# Sheet1.net
KiCad netlist of a schematic drawn in Altium Designer
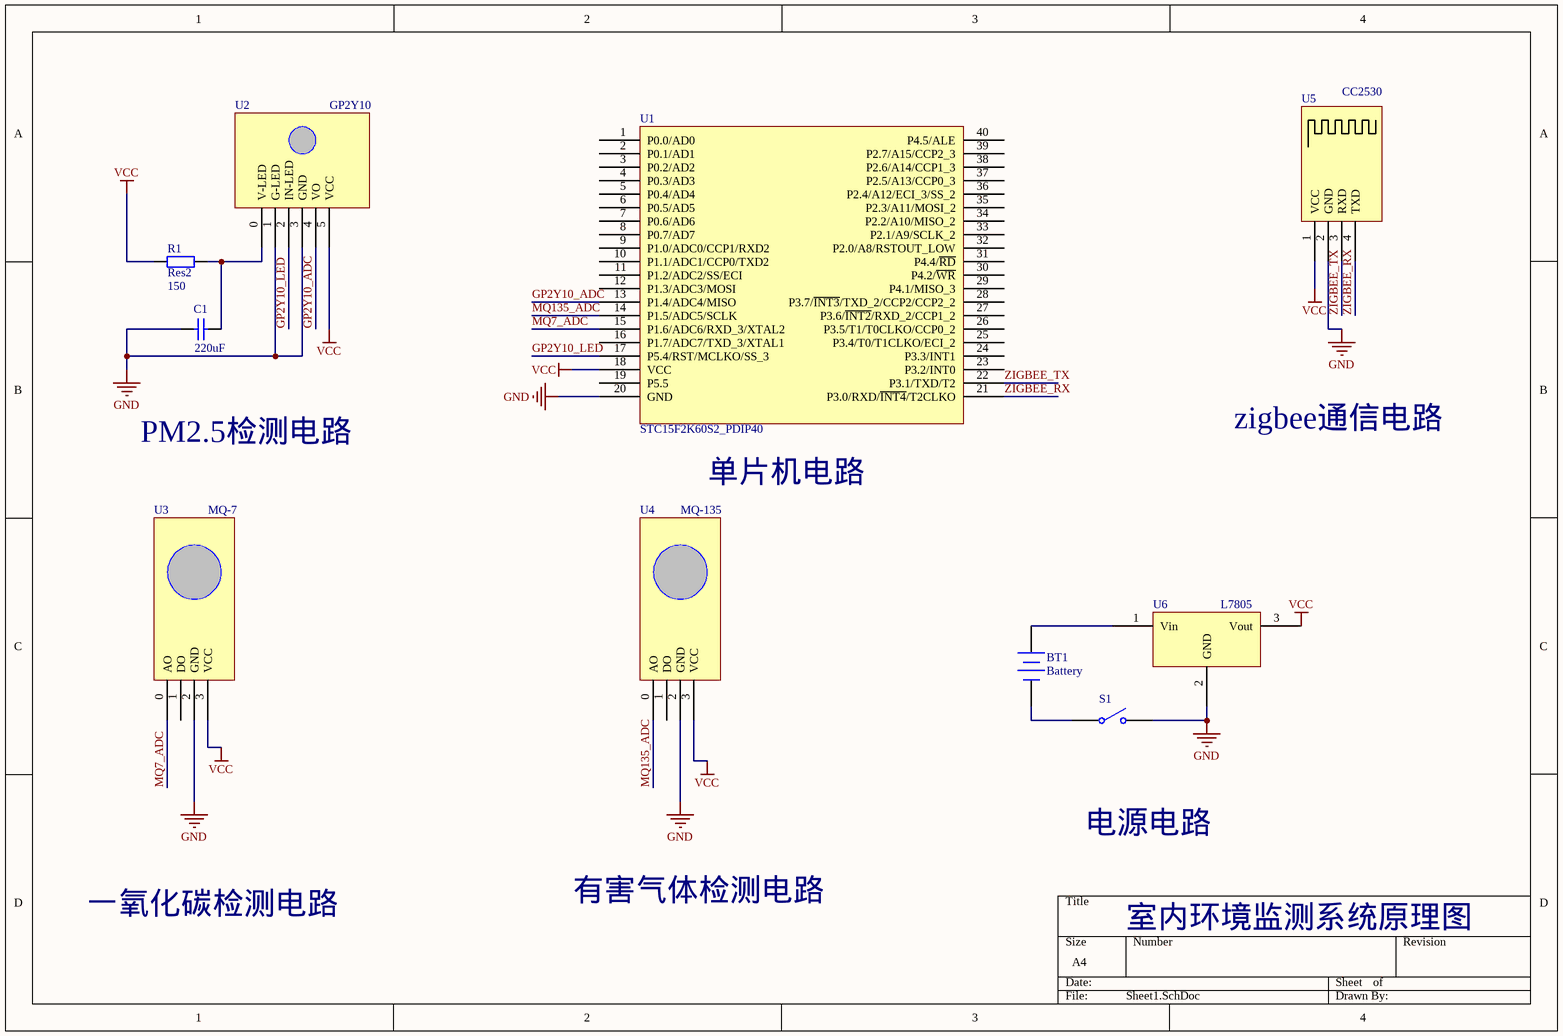
[diagram p0: Sheet1.SchDoc]

(export (version "E")
  (design (tool "Eeschema 10.0.6"))
  (components
    (comp (ref "BT1")
      (value "Battery")
      (footprint "BAT-2")
      (description "Multicell Battery")
      (fields (field (name "PUBLISHER") "Altium Limited"))
      (libsource (lib "Miscellaneous Devices") (part "Battery"))
    )
    (comp (ref "C1")
      (value "220uF")
      (footprint "RAD-0.3")
      (description "Capacitor")
      (fields (field (name "Comment") "Cap") (field (name "PUBLISHER") "Altium Limited"))
      (libsource (lib "Miscellaneous Devices") (part "Cap"))
    )
    (comp (ref "GP2Y10") (value "U2") (libsource (lib "Schlib1") (part "GP2Y10")))
    (comp (ref "R1")
      (value "Res2")
      (footprint "AXIAL-0.4")
      (description "Resistor")
      (fields (field (name "ALTIUM_VALUE") "150") (field (name "PUBLISHER") "Altium Limited"))
      (libsource (lib "Miscellaneous Devices") (part "Res2"))
    )
    (comp (ref "S1")
      (value "SW-SPST")
      (footprint "SPST-2")
      (description "Single-Pole, Single-Throw Switch")
      (fields (field (name "PUBLISHER") "Altium Limited"))
      (libsource (lib "Miscellaneous Devices") (part "SW-SPST"))
    )
    (comp (ref "U1")
      (value "STC15F2K60S2_PDIP40")
      (footprint "DIP40")
      (libsource (lib "stcmcu_altium_lib") (part "STC15F2K60S2_PDIP40"))
    )
    (comp (ref "U3") (value "MQ-7") (libsource (lib "Schlib1") (part "MQ-")))
    (comp (ref "U4") (value "MQ-135") (libsource (lib "Schlib1") (part "MQ-")))
    (comp (ref "U5") (value "CC2530") (libsource (lib "Schlib1") (part "CC2530")))
    (comp (ref "U6") (value "L7805") (libsource (lib "Schlib1") (part "L7805")))
  )
  (nets
    (net (code "1") (name "/GP2Y10_ADC") (class "Default")
      (node (ref "GP2Y10") (pin "4") (pinfunction "VO_4") (pintype "passive"))
      (node (ref "U1") (pin "13") (pinfunction "P1.4/ADC4/MISO_13") (pintype "passive"))
    )
    (net (code "2") (name "/GP2Y10_LED") (class "Default")
      (node (ref "GP2Y10") (pin "2") (pinfunction "IN-LED_2") (pintype "passive"))
      (node (ref "U1") (pin "17") (pinfunction "P5.4/RST/MCLKO/SS_3_17") (pintype "passive"))
    )
    (net (code "3") (name "/MQ7_ADC") (class "Default")
      (node (ref "U1") (pin "15") (pinfunction "P1.6/ADC6/RXD_3/XTAL2_15") (pintype "passive"))
      (node (ref "U3") (pin "0") (pinfunction "AO_0") (pintype "passive"))
    )
    (net (code "4") (name "/MQ135_ADC") (class "Default")
      (node (ref "U1") (pin "14") (pinfunction "P1.5/ADC5/SCLK_14") (pintype "passive"))
      (node (ref "U4") (pin "0") (pinfunction "AO_0") (pintype "passive"))
    )
    (net (code "5") (name "/ZIGBEE_RX") (class "Default")
      (node (ref "U1") (pin "21") (pinfunction "P3.0/RXD/~{INT4}/T2CLKO_21") (pintype "passive"))
      (node (ref "U5") (pin "4") (pinfunction "TXD_4") (pintype "passive"))
    )
    (net (code "6") (name "/ZIGBEE_TX") (class "Default")
      (node (ref "U1") (pin "22") (pinfunction "P3.1/TXD/T2_22") (pintype "passive"))
      (node (ref "U5") (pin "3") (pinfunction "RXD_3") (pintype "passive"))
    )
    (net (code "7") (name "GND") (class "Default")
      (node (ref "C1") (pin "1") (pinfunction "1_1") (pintype "passive"))
      (node (ref "GP2Y10") (pin "1") (pinfunction "G-LED_1") (pintype "passive"))
      (node (ref "GP2Y10") (pin "3") (pinfunction "GND_3") (pintype "passive"))
      (node (ref "S1") (pin "2") (pinfunction "NO_2") (pintype "passive"))
      (node (ref "U1") (pin "20") (pinfunction "GND_20") (pintype "passive"))
      (node (ref "U3") (pin "2") (pinfunction "GND_2") (pintype "passive"))
      (node (ref "U4") (pin "2") (pinfunction "GND_2") (pintype "passive"))
      (node (ref "U5") (pin "2") (pinfunction "GND_2") (pintype "passive"))
      (node (ref "U6") (pin "2") (pinfunction "GND_2") (pintype "passive"))
    )
    (net (code "8") (name "Net-(BT1-+)") (class "Default")
      (node (ref "BT1") (pin "1") (pinfunction "+_1") (pintype "passive"))
      (node (ref "U6") (pin "1") (pinfunction "Vin_1") (pintype "passive"))
    )
    (net (code "9") (name "Net-(BT1--)") (class "Default")
      (node (ref "BT1") (pin "2") (pinfunction "-_2") (pintype "passive"))
      (node (ref "S1") (pin "1") (pinfunction "COMMON_1") (pintype "passive"))
    )
    (net (code "10") (name "Net-(GP2Y10-V-LED)") (class "Default")
      (node (ref "C1") (pin "2") (pinfunction "2_2") (pintype "passive"))
      (node (ref "GP2Y10") (pin "0") (pinfunction "V-LED_0") (pintype "passive"))
      (node (ref "R1") (pin "2") (pinfunction "2_2") (pintype "passive"))
    )
    (net (code "11") (name "VCC") (class "Default")
      (node (ref "GP2Y10") (pin "5") (pinfunction "VCC_5") (pintype "passive"))
      (node (ref "R1") (pin "1") (pinfunction "1_1") (pintype "passive"))
      (node (ref "U1") (pin "18") (pinfunction "VCC_18") (pintype "passive"))
      (node (ref "U3") (pin "3") (pinfunction "VCC_3") (pintype "passive"))
      (node (ref "U4") (pin "3") (pinfunction "VCC_3") (pintype "passive"))
      (node (ref "U5") (pin "1") (pinfunction "VCC_1") (pintype "passive"))
      (node (ref "U6") (pin "3") (pinfunction "Vout_3") (pintype "passive"))
    )
    (net (code "12") (name "unconnected-(U1-P0.0{slash}AD0-Pad1)") (class "Default")
      (node (ref "U1") (pin "1") (pinfunction "P0.0/AD0_1") (pintype "passive"))
    )
    (net (code "13") (name "unconnected-(U1-P0.1{slash}AD1-Pad2)") (class "Default")
      (node (ref "U1") (pin "2") (pinfunction "P0.1/AD1_2") (pintype "passive"))
    )
    (net (code "14") (name "unconnected-(U1-P0.2{slash}AD2-Pad3)") (class "Default")
      (node (ref "U1") (pin "3") (pinfunction "P0.2/AD2_3") (pintype "passive"))
    )
    (net (code "15") (name "unconnected-(U1-P0.3{slash}AD3-Pad4)") (class "Default")
      (node (ref "U1") (pin "4") (pinfunction "P0.3/AD3_4") (pintype "passive"))
    )
    (net (code "16") (name "unconnected-(U1-P0.4{slash}AD4-Pad5)") (class "Default")
      (node (ref "U1") (pin "5") (pinfunction "P0.4/AD4_5") (pintype "passive"))
    )
    (net (code "17") (name "unconnected-(U1-P0.5{slash}AD5-Pad6)") (class "Default")
      (node (ref "U1") (pin "6") (pinfunction "P0.5/AD5_6") (pintype "passive"))
    )
    (net (code "18") (name "unconnected-(U1-P0.6{slash}AD6-Pad7)") (class "Default")
      (node (ref "U1") (pin "7") (pinfunction "P0.6/AD6_7") (pintype "passive"))
    )
    (net (code "19") (name "unconnected-(U1-P0.7{slash}AD7-Pad8)") (class "Default")
      (node (ref "U1") (pin "8") (pinfunction "P0.7/AD7_8") (pintype "passive"))
    )
    (net (code "20") (name "unconnected-(U1-P1.0{slash}ADC0{slash}CCP1{slash}RXD2-Pad9)") (class "Default")
      (node (ref "U1") (pin "9") (pinfunction "P1.0/ADC0/CCP1/RXD2_9") (pintype "passive"))
    )
    (net (code "21") (name "unconnected-(U1-P1.1{slash}ADC1{slash}CCP0{slash}TXD2-Pad10)") (class "Default")
      (node (ref "U1") (pin "10") (pinfunction "P1.1/ADC1/CCP0/TXD2_10") (pintype "passive"))
    )
    (net (code "22") (name "unconnected-(U1-P1.2{slash}ADC2{slash}SS{slash}ECI-Pad11)") (class "Default")
      (node (ref "U1") (pin "11") (pinfunction "P1.2/ADC2/SS/ECI_11") (pintype "passive"))
    )
    (net (code "23") (name "unconnected-(U1-P1.3{slash}ADC3{slash}MOSI-Pad12)") (class "Default")
      (node (ref "U1") (pin "12") (pinfunction "P1.3/ADC3/MOSI_12") (pintype "passive"))
    )
    (net (code "24") (name "unconnected-(U1-P1.7{slash}ADC7{slash}TXD_3{slash}XTAL1-Pad16)") (class "Default")
      (node (ref "U1") (pin "16") (pinfunction "P1.7/ADC7/TXD_3/XTAL1_16") (pintype "passive"))
    )
    (net (code "25") (name "unconnected-(U1-P2.0{slash}A8{slash}RSTOUT_LOW-Pad32)") (class "Default")
      (node (ref "U1") (pin "32") (pinfunction "P2.0/A8/RSTOUT_LOW_32") (pintype "passive"))
    )
    (net (code "26") (name "unconnected-(U1-P2.1{slash}A9{slash}SCLK_2-Pad33)") (class "Default")
      (node (ref "U1") (pin "33") (pinfunction "P2.1/A9/SCLK_2_33") (pintype "passive"))
    )
    (net (code "27") (name "unconnected-(U1-P2.2{slash}A10{slash}MISO_2-Pad34)") (class "Default")
      (node (ref "U1") (pin "34") (pinfunction "P2.2/A10/MISO_2_34") (pintype "passive"))
    )
    (net (code "28") (name "unconnected-(U1-P2.3{slash}A11{slash}MOSI_2-Pad35)") (class "Default")
      (node (ref "U1") (pin "35") (pinfunction "P2.3/A11/MOSI_2_35") (pintype "passive"))
    )
    (net (code "29") (name "unconnected-(U1-P2.4{slash}A12{slash}ECI_3{slash}SS_2-Pad36)") (class "Default")
      (node (ref "U1") (pin "36") (pinfunction "P2.4/A12/ECI_3/SS_2_36") (pintype "passive"))
    )
    (net (code "30") (name "unconnected-(U1-P2.5{slash}A13{slash}CCP0_3-Pad37)") (class "Default")
      (node (ref "U1") (pin "37") (pinfunction "P2.5/A13/CCP0_3_37") (pintype "passive"))
    )
    (net (code "31") (name "unconnected-(U1-P2.6{slash}A14{slash}CCP1_3-Pad38)") (class "Default")
      (node (ref "U1") (pin "38") (pinfunction "P2.6/A14/CCP1_3_38") (pintype "passive"))
    )
    (net (code "32") (name "unconnected-(U1-P2.7{slash}A15{slash}CCP2_3-Pad39)") (class "Default")
      (node (ref "U1") (pin "39") (pinfunction "P2.7/A15/CCP2_3_39") (pintype "passive"))
    )
    (net (code "33") (name "unconnected-(U1-P3.2{slash}INT0-Pad23)") (class "Default")
      (node (ref "U1") (pin "23") (pinfunction "P3.2/INT0_23") (pintype "passive"))
    )
    (net (code "34") (name "unconnected-(U1-P3.3{slash}INT1-Pad24)") (class "Default")
      (node (ref "U1") (pin "24") (pinfunction "P3.3/INT1_24") (pintype "passive"))
    )
    (net (code "35") (name "unconnected-(U1-P3.4{slash}T0{slash}T1CLKO{slash}ECI_2-Pad25)") (class "Default")
      (node (ref "U1") (pin "25") (pinfunction "P3.4/T0/T1CLKO/ECI_2_25") (pintype "passive"))
    )
    (net (code "36") (name "unconnected-(U1-P3.5{slash}T1{slash}T0CLKO{slash}CCP0_2-Pad26)") (class "Default")
      (node (ref "U1") (pin "26") (pinfunction "P3.5/T1/T0CLKO/CCP0_2_26") (pintype "passive"))
    )
    (net (code "37") (name "unconnected-(U1-P3.6{slash}~{INT2}{slash}RXD_2{slash}CCP1_2-Pad27)") (class "Default")
      (node (ref "U1") (pin "27") (pinfunction "P3.6/~{INT2}/RXD_2/CCP1_2_27") (pintype "passive"))
    )
    (net (code "38") (name "unconnected-(U1-P3.7{slash}~{INT3}{slash}TXD_2{slash}CCP2{slash}CCP2_2-Pad28)") (class "Default")
      (node (ref "U1") (pin "28") (pinfunction "P3.7/~{INT3}/TXD_2/CCP2/CCP2_2_28") (pintype "passive"))
    )
    (net (code "39") (name "unconnected-(U1-P4.1{slash}MISO_3-Pad29)") (class "Default")
      (node (ref "U1") (pin "29") (pinfunction "P4.1/MISO_3_29") (pintype "passive"))
    )
    (net (code "40") (name "unconnected-(U1-P4.2{slash}~{WR}-Pad30)") (class "Default")
      (node (ref "U1") (pin "30") (pinfunction "P4.2/~{WR}_30") (pintype "passive"))
    )
    (net (code "41") (name "unconnected-(U1-P4.4{slash}~{RD}-Pad31)") (class "Default")
      (node (ref "U1") (pin "31") (pinfunction "P4.4/~{RD}_31") (pintype "passive"))
    )
    (net (code "42") (name "unconnected-(U1-P4.5{slash}ALE-Pad40)") (class "Default")
      (node (ref "U1") (pin "40") (pinfunction "P4.5/ALE_40") (pintype "passive"))
    )
    (net (code "43") (name "unconnected-(U1-P5.5-Pad19)") (class "Default")
      (node (ref "U1") (pin "19") (pinfunction "P5.5_19") (pintype "passive"))
    )
    (net (code "44") (name "unconnected-(U3-DO-Pad1)") (class "Default")
      (node (ref "U3") (pin "1") (pinfunction "DO_1") (pintype "passive"))
    )
    (net (code "45") (name "unconnected-(U4-DO-Pad1)") (class "Default")
      (node (ref "U4") (pin "1") (pinfunction "DO_1") (pintype "passive"))
    )
  )
)
